# ES.net
KiCad netlist of a schematic drawn in Altium Designer
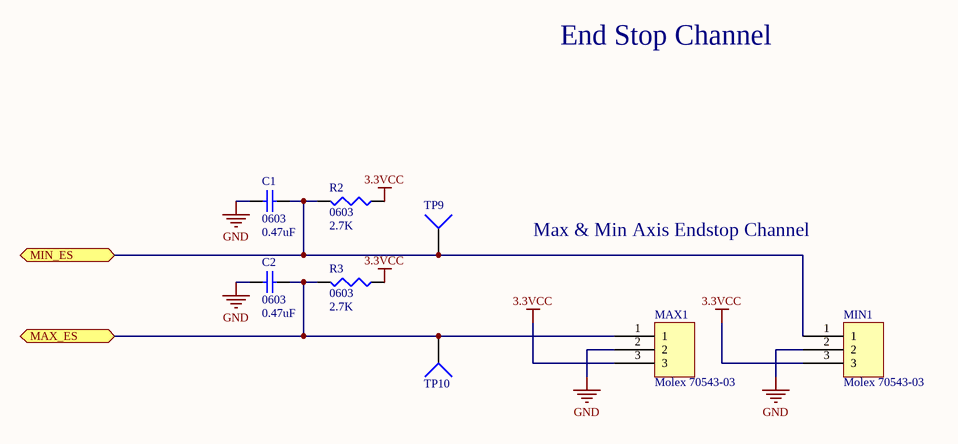
[diagram p0: ES.SchDoc]

(export (version "E")
  (design (tool "Eeschema 10.0.6"))
  (components
    (comp (ref "C1")
      (value "0603")
      (footprint "1608[0603]")
      (description "Capacitor (Semiconductor SIM Model)")
      (fields (field (name "ALTIUM_VALUE") "0.47uF") (field (name "PUBLISHER") "Altium Limited"))
      (libsource (lib "Miscellaneous Devices") (part "Cap Semi"))
    )
    (comp (ref "C2")
      (value "0603")
      (footprint "1608[0603]")
      (description "Capacitor (Semiconductor SIM Model)")
      (fields (field (name "ALTIUM_VALUE") "0.47uF") (field (name "PUBLISHER") "Altium Limited"))
      (libsource (lib "Miscellaneous Devices") (part "Cap Semi"))
    )
    (comp (ref "MAX1")
      (value "Molex 70543-03")
      (footprint "70543-03")
      (libsource (lib "RADMBo Schematic Library") (part "Molex Endstop"))
    )
    (comp (ref "MIN1")
      (value "Molex 70543-03")
      (footprint "70543-03")
      (libsource (lib "RADMBo Schematic Library") (part "Molex Endstop"))
    )
    (comp (ref "R2")
      (value "0603")
      (footprint "J1-0603")
      (description "Resistor")
      (fields (field (name "ALTIUM_VALUE") "2.7K") (field (name "PUBLISHER") "Altium Limited"))
      (libsource (lib "Miscellaneous Devices") (part "Res3"))
    )
    (comp (ref "R3")
      (value "0603")
      (footprint "J1-0603")
      (description "Resistor")
      (fields (field (name "ALTIUM_VALUE") "2.7K") (field (name "PUBLISHER") "Altium Limited"))
      (libsource (lib "Miscellaneous Devices") (part "Res3"))
    )
    (comp (ref "TP9")
      (value "TP4")
      (footprint "TP-2")
      (description "Socket")
      (fields (field (name "PUBLISHER") "Altium Limited"))
      (libsource (lib "ZMBo Schematic Library") (part "Socket"))
    )
    (comp (ref "TP10")
      (value "TP4")
      (footprint "TP-2")
      (description "Socket")
      (fields (field (name "PUBLISHER") "Altium Limited"))
      (libsource (lib "ZMBo Schematic Library") (part "Socket"))
    )
  )
  (nets
    (net (code "1") (name "/MAX_ES") (class "Default")
      (node (ref "C2") (pin "1") (pinfunction "1_1") (pintype "passive"))
      (node (ref "MAX1") (pin "1") (pinfunction "1_1") (pintype "passive"))
      (node (ref "R3") (pin "2") (pinfunction "2_2") (pintype "passive"))
      (node (ref "TP10") (pin "1") (pinfunction "1_1") (pintype "passive"))
    )
    (net (code "2") (name "/MIN_ES") (class "Default")
      (node (ref "C1") (pin "1") (pinfunction "1_1") (pintype "passive"))
      (node (ref "MIN1") (pin "1") (pinfunction "1_1") (pintype "passive"))
      (node (ref "R2") (pin "2") (pinfunction "2_2") (pintype "passive"))
      (node (ref "TP9") (pin "1") (pinfunction "1_1") (pintype "passive"))
    )
    (net (code "3") (name "3.3VCC") (class "Default")
      (node (ref "MAX1") (pin "3") (pinfunction "3_3") (pintype "passive"))
      (node (ref "MIN1") (pin "3") (pinfunction "3_3") (pintype "passive"))
      (node (ref "R2") (pin "1") (pinfunction "1_1") (pintype "passive"))
      (node (ref "R3") (pin "1") (pinfunction "1_1") (pintype "passive"))
    )
    (net (code "4") (name "GND") (class "Default")
      (node (ref "C1") (pin "2") (pinfunction "2_2") (pintype "passive"))
      (node (ref "C2") (pin "2") (pinfunction "2_2") (pintype "passive"))
      (node (ref "MAX1") (pin "2") (pinfunction "2_2") (pintype "passive"))
      (node (ref "MIN1") (pin "2") (pinfunction "2_2") (pintype "passive"))
    )
  )
)
